# MyRC.net
KiCad netlist of a schematic drawn in Altium Designer
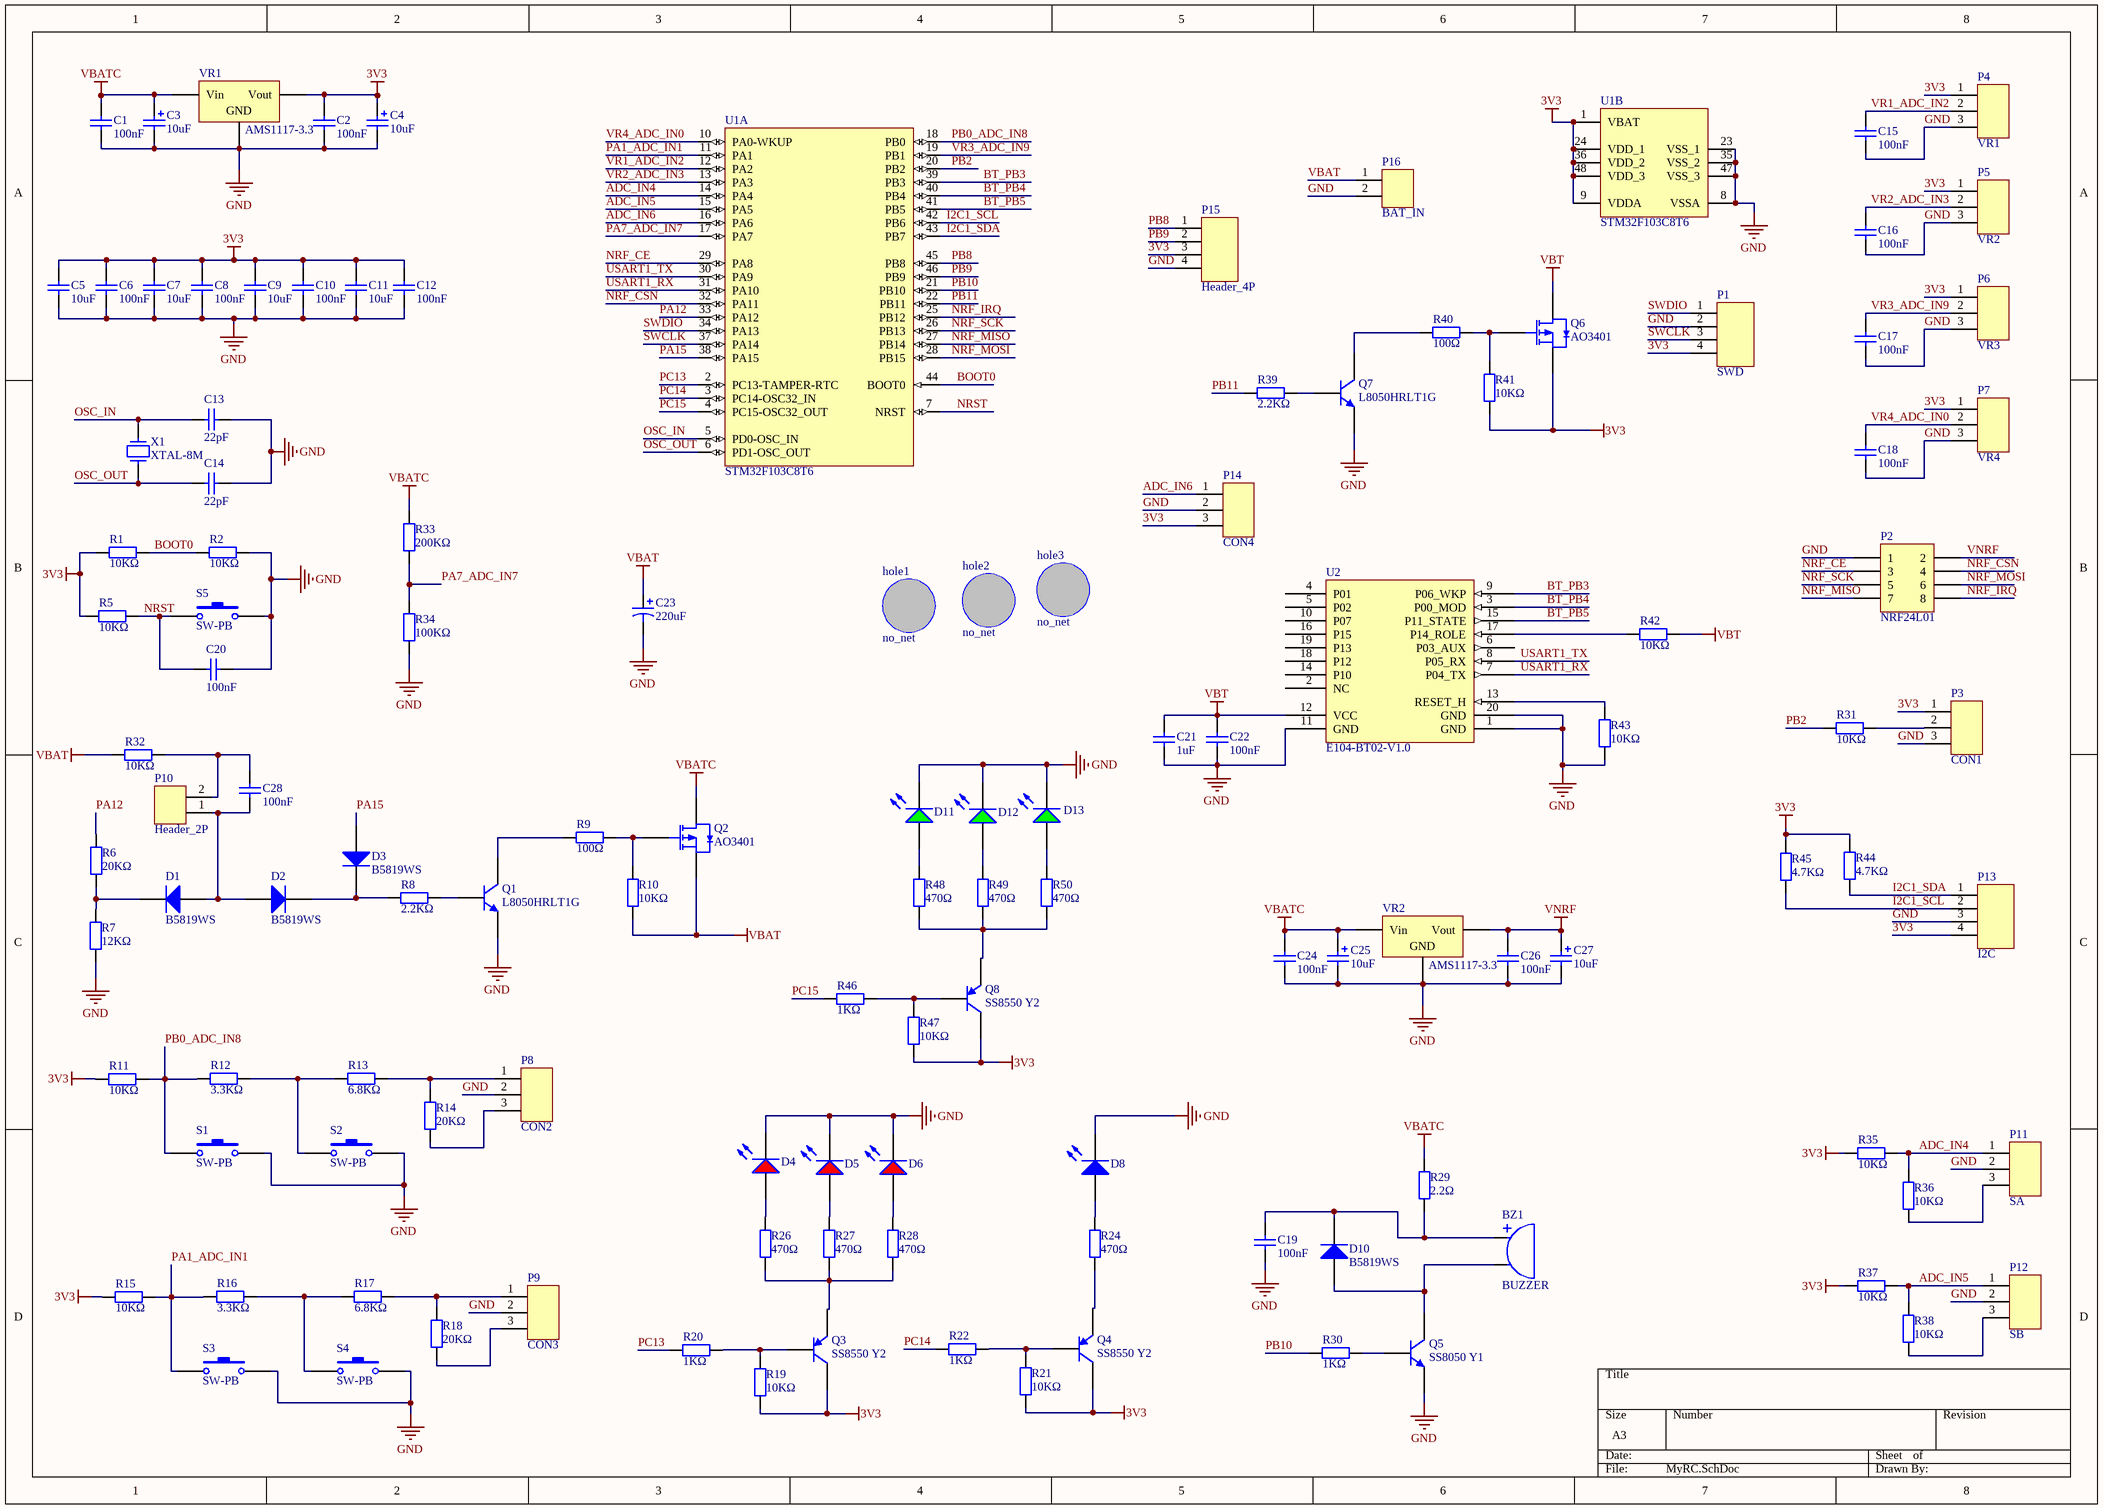
[diagram p0: MyRC.SchDoc]

(export (version "E")
  (design (tool "Eeschema 10.0.6"))
  (components
    (comp (ref "BZ1")
      (value "BUZZER")
      (footprint "BUZ_9MM")
      (description "Buzzer")
      (libsource (lib "General") (part "BUZZER"))
    )
    (comp (ref "C1")
      (value "100nF")
      (footprint "0603_C")
      (description "贴片电容")
      (libsource (lib "Miscellaneous Devices LC") (part "0603 220nF (224) 10% 25V"))
    )
    (comp (ref "C2")
      (value "100nF")
      (footprint "0603_C")
      (description "贴片电容")
      (libsource (lib "Miscellaneous Devices LC") (part "0603 220nF (224) 10% 25V"))
    )
    (comp (ref "C3")
      (value "10uF")
      (footprint "CASE-A_3216")
      (description "钽电容")
      (libsource (lib "Miscellaneous Devices LC") (part "3216 10uF (106) 10% 16V"))
    )
    (comp (ref "C4")
      (value "10uF")
      (footprint "CASE-A_3216")
      (description "钽电容")
      (libsource (lib "Miscellaneous Devices LC") (part "3216 10uF (106) 10% 16V"))
    )
    (comp (ref "C5")
      (value "10uF")
      (footprint "0603_C")
      (description "贴片电容")
      (libsource (lib "Miscellaneous Devices LC") (part "0603 2.2uF (225) 10% 16V"))
    )
    (comp (ref "C6")
      (value "100nF")
      (footprint "0603_C")
      (description "贴片电容")
      (libsource (lib "Miscellaneous Devices LC") (part "0603 2.2uF (225) 10% 16V"))
    )
    (comp (ref "C7")
      (value "10uF")
      (footprint "0603_C")
      (description "贴片电容")
      (libsource (lib "Miscellaneous Devices LC") (part "0603 2.2uF (225) 10% 16V"))
    )
    (comp (ref "C8")
      (value "100nF")
      (footprint "0603_C")
      (description "贴片电容")
      (libsource (lib "Miscellaneous Devices LC") (part "0603 2.2uF (225) 10% 16V"))
    )
    (comp (ref "C9")
      (value "10uF")
      (footprint "0603_C")
      (description "贴片电容")
      (libsource (lib "Miscellaneous Devices LC") (part "0603 2.2uF (225) 10% 16V"))
    )
    (comp (ref "C10")
      (value "100nF")
      (footprint "0603_C")
      (description "贴片电容")
      (libsource (lib "Miscellaneous Devices LC") (part "0603 2.2uF (225) 10% 16V"))
    )
    (comp (ref "C11")
      (value "10uF")
      (footprint "0603_C")
      (description "贴片电容")
      (libsource (lib "Miscellaneous Devices LC") (part "0603 2.2uF (225) 10% 16V"))
    )
    (comp (ref "C12")
      (value "100nF")
      (footprint "0603_C")
      (description "贴片电容")
      (libsource (lib "Miscellaneous Devices LC") (part "0603 2.2uF (225) 10% 16V"))
    )
    (comp (ref "C13")
      (value "22pF")
      (footprint "0603_C")
      (description "贴片电容")
      (libsource (lib "Miscellaneous Devices LC") (part "0603 2.2nF (222) 10% 50V"))
    )
    (comp (ref "C14")
      (value "22pF")
      (footprint "0603_C")
      (description "贴片电容")
      (libsource (lib "Miscellaneous Devices LC") (part "0603 2.2nF (222) 10% 50V"))
    )
    (comp (ref "C15")
      (value "100nF")
      (footprint "0603_C")
      (description "贴片电容")
      (libsource (lib "Miscellaneous Devices LC") (part "0603 2.2uF (225) 10% 16V"))
    )
    (comp (ref "C16")
      (value "100nF")
      (footprint "0603_C")
      (description "贴片电容")
      (libsource (lib "Miscellaneous Devices LC") (part "0603 2.2uF (225) 10% 16V"))
    )
    (comp (ref "C17")
      (value "100nF")
      (footprint "0603_C")
      (description "贴片电容")
      (libsource (lib "Miscellaneous Devices LC") (part "0603 2.2uF (225) 10% 16V"))
    )
    (comp (ref "C18")
      (value "100nF")
      (footprint "0603_C")
      (description "贴片电容")
      (libsource (lib "Miscellaneous Devices LC") (part "0603 2.2uF (225) 10% 16V"))
    )
    (comp (ref "C19")
      (value "100nF")
      (footprint "0603_C")
      (description "贴片电容")
      (libsource (lib "Miscellaneous Devices LC") (part "0603 2.2uF (225) 10% 16V"))
    )
    (comp (ref "C20")
      (value "100nF")
      (footprint "0603_C")
      (description "贴片电容")
      (libsource (lib "Miscellaneous Devices LC") (part "0603 2.2uF (225) 10% 16V"))
    )
    (comp (ref "C21")
      (value "1uF")
      (footprint "0603_C")
      (description "贴片电容")
      (libsource (lib "Miscellaneous Devices LC") (part "0603 2.2uF (225) 10% 16V"))
    )
    (comp (ref "C22")
      (value "100nF")
      (footprint "0603_C")
      (description "贴片电容")
      (libsource (lib "Miscellaneous Devices LC") (part "0603 2.2uF (225) 10% 16V"))
    )
    (comp (ref "C23")
      (value "220uF")
      (footprint "SMD_220uF")
      (description "Polarized Capacitor (Surface Mount)")
      (fields (field (name "Comment") "Cap Pol3") (field (name "PUBLISHER") "Altium Limited"))
      (libsource (lib "Miscellaneous Devices") (part "Cap Pol3"))
    )
    (comp (ref "C24")
      (value "100nF")
      (footprint "0603_C")
      (description "贴片电容")
      (libsource (lib "Miscellaneous Devices LC") (part "0603 220nF (224) 10% 25V"))
    )
    (comp (ref "C25")
      (value "10uF")
      (footprint "CASE-A_3216")
      (description "钽电容")
      (libsource (lib "Miscellaneous Devices LC") (part "3216 10uF (106) 10% 16V"))
    )
    (comp (ref "C26")
      (value "100nF")
      (footprint "0603_C")
      (description "贴片电容")
      (libsource (lib "Miscellaneous Devices LC") (part "0603 220nF (224) 10% 25V"))
    )
    (comp (ref "C27")
      (value "10uF")
      (footprint "CASE-A_3216")
      (description "钽电容")
      (libsource (lib "Miscellaneous Devices LC") (part "3216 10uF (106) 10% 16V"))
    )
    (comp (ref "C28")
      (value "100nF")
      (footprint "0603_C")
      (description "贴片电容")
      (libsource (lib "Miscellaneous Devices LC") (part "0603 1.2nF (122) 10% 50V"))
    )
    (comp (ref "D1")
      (value "B5819WS")
      (footprint "SOD-323")
      (description "二极管")
      (libsource (lib "Miscellaneous Devices LC") (part "SOD-323 1N4148WS T4"))
    )
    (comp (ref "D2")
      (value "B5819WS")
      (footprint "SOD-323")
      (description "二极管")
      (libsource (lib "Miscellaneous Devices LC") (part "SOD-323 1N4148WS T4"))
    )
    (comp (ref "D3")
      (value "B5819WS")
      (footprint "SOD-323")
      (description "二极管")
      (libsource (lib "Miscellaneous Devices LC") (part "SOD-323 1N4148WS T4"))
    )
    (comp (ref "D4")
      (value "红灯 0603")
      (footprint "0603_LED_S1")
      (description "发光二极管")
      (libsource (lib "Miscellaneous Devices LC") (part "0603 红灯"))
    )
    (comp (ref "D5")
      (value "红灯 0603")
      (footprint "0603_LED_S1")
      (description "发光二极管")
      (libsource (lib "Miscellaneous Devices LC") (part "0603 红灯"))
    )
    (comp (ref "D6")
      (value "红灯 0603")
      (footprint "0603_LED_S1")
      (description "发光二极管")
      (libsource (lib "Miscellaneous Devices LC") (part "0603 红灯"))
    )
    (comp (ref "D8")
      (value "蓝灯 0603")
      (footprint "0603_LED_S1")
      (description "发光二极管")
      (libsource (lib "Miscellaneous Devices LC") (part "0603 蓝灯"))
    )
    (comp (ref "D10")
      (value "B5819WS")
      (footprint "SOD-323")
      (description "二极管")
      (libsource (lib "Miscellaneous Devices LC") (part "SOD-323 1N4148WS T4"))
    )
    (comp (ref "D11")
      (value "绿灯 0603")
      (footprint "0603_LED_S1")
      (description "发光二极管")
      (libsource (lib "Miscellaneous Devices LC") (part "0603 绿灯"))
    )
    (comp (ref "D12")
      (value "绿灯 0603")
      (footprint "0603_LED_S1")
      (description "发光二极管")
      (libsource (lib "Miscellaneous Devices LC") (part "0603 绿灯"))
    )
    (comp (ref "D13")
      (value "绿灯 0603")
      (footprint "0603_LED_S1")
      (description "发光二极管")
      (libsource (lib "Miscellaneous Devices LC") (part "0603 绿灯"))
    )
    (comp (ref "hole1") (value "no_net") (footprint "Screw_holes") (libsource (lib "MyRC") (part "no_net")))
    (comp (ref "hole2") (value "no_net") (footprint "Screw_holes") (libsource (lib "MyRC") (part "no_net")))
    (comp (ref "hole3") (value "no_net") (footprint "Screw_holes") (libsource (lib "MyRC") (part "no_net")))
    (comp (ref "P1") (value "SWD") (footprint "SMD_1.25T_4P") (libsource (lib "MyRC") (part "Header_4P")))
    (comp (ref "P2")
      (value "NRF24L01")
      (footprint "HDR2X4")
      (description "Header, 4-Pin, Dual row")
      (fields (field (name "PUBLISHER") "Altium Limited"))
      (libsource (lib "Miscellaneous Connectors") (part "Header 4X2"))
    )
    (comp (ref "P3")
      (value "CON1")
      (footprint "SMD_1.25T_3P")
      (description "油门微动")
      (libsource (lib "MyRC") (part "Header_3P"))
    )
    (comp (ref "P4") (value "VR1") (footprint "SMD_1.25T_3P") (libsource (lib "MyRC") (part "Header_3P")))
    (comp (ref "P5") (value "VR2") (footprint "SMD_1.25T_3P") (libsource (lib "MyRC") (part "Header_3P")))
    (comp (ref "P6") (value "VR3") (footprint "SMD_1.25T_3P") (libsource (lib "MyRC") (part "Header_3P")))
    (comp (ref "P7") (value "VR4") (footprint "SMD_1.25T_3P") (libsource (lib "MyRC") (part "Header_3P")))
    (comp (ref "P8") (value "CON2") (footprint "SMD_1.25T_3P") (libsource (lib "MyRC") (part "Header_3P")))
    (comp (ref "P9") (value "CON3") (footprint "SMD_1.25T_3P") (libsource (lib "MyRC") (part "Header_3P")))
    (comp (ref "P10")
      (value "Header_2P")
      (footprint "SMD_1.25T_2P")
      (libsource (lib "") (part "Header_2P_1"))
    )
    (comp (ref "P11") (value "SA") (footprint "SMD_1.25T_3P") (libsource (lib "MyRC") (part "Header_3P")))
    (comp (ref "P12") (value "SB") (footprint "SMD_1.25T_3P") (libsource (lib "MyRC") (part "Header_3P")))
    (comp (ref "P13") (value "I2C") (footprint "SMD_1.25T_4P") (libsource (lib "MyRC") (part "Header_4P")))
    (comp (ref "P14") (value "CON4") (footprint "SMD_1.25T_3P") (libsource (lib "MyRC") (part "Header_3P")))
    (comp (ref "P15")
      (value "Header_4P")
      (footprint "SMD_1.25T_4P")
      (libsource (lib "MyRC") (part "Header_4P"))
    )
    (comp (ref "P16") (value "BAT_IN") (footprint "BAT_IN") (libsource (lib "MyRC") (part "Header_2P")))
    (comp (ref "Q1")
      (value "L8050HRLT1G")
      (footprint "SOT-23(SOT-23-3)")
      (description "三极管")
      (libsource (lib "Miscellaneous Devices LC") (part "SOT-23 SS8050 Y1"))
    )
    (comp (ref "Q2")
      (value "AO3401")
      (footprint "SOT-23-3L")
      (description "MOS(场效应管)")
      (libsource (lib "Miscellaneous Devices LC") (part "AO3401A P道沟 X13A15 SOT-23"))
    )
    (comp (ref "Q3")
      (value "SS8550 Y2")
      (footprint "SOT-23(SOT-23-3)")
      (description "三极管")
      (libsource (lib "Miscellaneous Devices LC") (part "SOT-23 SS8550 Y2"))
    )
    (comp (ref "Q4")
      (value "SS8550 Y2")
      (footprint "SOT-23(SOT-23-3)")
      (description "三极管")
      (libsource (lib "Miscellaneous Devices LC") (part "SOT-23 SS8550 Y2"))
    )
    (comp (ref "Q5")
      (value "SS8050 Y1")
      (footprint "SOT-23(SOT-23-3)")
      (description "三极管")
      (libsource (lib "Miscellaneous Devices LC") (part "SOT-23 SS8050 Y1"))
    )
    (comp (ref "Q6")
      (value "AO3401")
      (footprint "SOT-23-3L")
      (description "MOS(场效应管)")
      (libsource (lib "Miscellaneous Devices LC") (part "AO3401A P道沟 X13A15 SOT-23"))
    )
    (comp (ref "Q7")
      (value "L8050HRLT1G")
      (footprint "SOT-23(SOT-23-3)")
      (description "三极管")
      (libsource (lib "Miscellaneous Devices LC") (part "SOT-23 SS8050 Y1"))
    )
    (comp (ref "Q8")
      (value "SS8550 Y2")
      (footprint "SOT-23(SOT-23-3)")
      (description "三极管")
      (libsource (lib "Miscellaneous Devices LC") (part "SOT-23 SS8550 Y2"))
    )
    (comp (ref "R1")
      (value "10KΩ")
      (footprint "0603_R")
      (description "贴片电阻")
      (libsource (lib "Miscellaneous Devices LC") (part "0603 3.6KΩ (3601) 1%"))
    )
    (comp (ref "R2")
      (value "10KΩ")
      (footprint "0603_R")
      (description "贴片电阻")
      (libsource (lib "Miscellaneous Devices LC") (part "0603 3.6KΩ (3601) 1%"))
    )
    (comp (ref "R5")
      (value "10KΩ")
      (footprint "0603_R")
      (description "贴片电阻")
      (libsource (lib "Miscellaneous Devices LC") (part "0603 2KΩ (2001) 1%"))
    )
    (comp (ref "R6")
      (value "20KΩ")
      (footprint "0603_R")
      (description "贴片电阻")
      (libsource (lib "Miscellaneous Devices LC") (part "0603 3KΩ (3001) 1%"))
    )
    (comp (ref "R7")
      (value "12KΩ")
      (footprint "0603_R")
      (description "贴片电阻")
      (libsource (lib "") (part "0603 3KΩ (3001) 1%_2"))
    )
    (comp (ref "R8")
      (value "2.2KΩ")
      (footprint "0603_R")
      (description "贴片电阻")
      (libsource (lib "") (part "0603 3KΩ (3001) 1%_3"))
    )
    (comp (ref "R9")
      (value "100Ω")
      (footprint "0603_R")
      (description "贴片电阻")
      (libsource (lib "") (part "0603 3KΩ (3001) 1%_1"))
    )
    (comp (ref "R10")
      (value "10KΩ")
      (footprint "0603_R")
      (description "贴片电阻")
      (libsource (lib "Miscellaneous Devices LC") (part "0603 3KΩ (3001) 1%"))
    )
    (comp (ref "R11")
      (value "10KΩ")
      (footprint "0603_R")
      (description "贴片电阻")
      (libsource (lib "") (part "0603 1Ω (1R00) 1%_2"))
    )
    (comp (ref "R12")
      (value "3.3KΩ")
      (footprint "0603_R")
      (description "贴片电阻")
      (libsource (lib "") (part "0603 1Ω (1R00) 1%_2"))
    )
    (comp (ref "R13")
      (value "6.8KΩ")
      (footprint "0603_R")
      (description "贴片电阻")
      (libsource (lib "") (part "0603 1Ω (1R00) 1%_2"))
    )
    (comp (ref "R14")
      (value "20KΩ")
      (footprint "0603_R")
      (description "贴片电阻")
      (libsource (lib "") (part "0603 1Ω (1R00) 1%_1"))
    )
    (comp (ref "R15")
      (value "10KΩ")
      (footprint "0603_R")
      (description "贴片电阻")
      (libsource (lib "") (part "0603 1Ω (1R00) 1%_2"))
    )
    (comp (ref "R16")
      (value "3.3KΩ")
      (footprint "0603_R")
      (description "贴片电阻")
      (libsource (lib "") (part "0603 1Ω (1R00) 1%_2"))
    )
    (comp (ref "R17")
      (value "6.8KΩ")
      (footprint "0603_R")
      (description "贴片电阻")
      (libsource (lib "") (part "0603 1Ω (1R00) 1%_2"))
    )
    (comp (ref "R18")
      (value "20KΩ")
      (footprint "0603_R")
      (description "贴片电阻")
      (libsource (lib "") (part "0603 1Ω (1R00) 1%_1"))
    )
    (comp (ref "R19")
      (value "10KΩ")
      (footprint "0603_R")
      (description "贴片电阻")
      (libsource (lib "Miscellaneous Devices LC") (part "0603 1Ω (1R00) 1%"))
    )
    (comp (ref "R20")
      (value "1KΩ")
      (footprint "0603_R")
      (description "贴片电阻")
      (libsource (lib "") (part "0603 1Ω (1R00) 1%_2"))
    )
    (comp (ref "R21")
      (value "10KΩ")
      (footprint "0603_R")
      (description "贴片电阻")
      (libsource (lib "Miscellaneous Devices LC") (part "0603 1Ω (1R00) 1%"))
    )
    (comp (ref "R22")
      (value "1KΩ")
      (footprint "0603_R")
      (description "贴片电阻")
      (libsource (lib "") (part "0603 1Ω (1R00) 1%_2"))
    )
    (comp (ref "R24")
      (value "470Ω")
      (footprint "0603_R")
      (description "贴片电阻")
      (libsource (lib "Miscellaneous Devices LC") (part "0603 1Ω (1R00) 1%"))
    )
    (comp (ref "R26")
      (value "470Ω")
      (footprint "0603_R")
      (description "贴片电阻")
      (libsource (lib "Miscellaneous Devices LC") (part "0603 1Ω (1R00) 1%"))
    )
    (comp (ref "R27")
      (value "470Ω")
      (footprint "0603_R")
      (description "贴片电阻")
      (libsource (lib "Miscellaneous Devices LC") (part "0603 1Ω (1R00) 1%"))
    )
    (comp (ref "R28")
      (value "470Ω")
      (footprint "0603_R")
      (description "贴片电阻")
      (libsource (lib "Miscellaneous Devices LC") (part "0603 1Ω (1R00) 1%"))
    )
    (comp (ref "R29")
      (value "2.2Ω")
      (footprint "0603_R")
      (description "贴片电阻")
      (libsource (lib "Miscellaneous Devices LC") (part "0603 1Ω (1R00) 1%"))
    )
    (comp (ref "R30")
      (value "1KΩ")
      (footprint "0603_R")
      (description "贴片电阻")
      (libsource (lib "") (part "0603 1Ω (1R00) 1%_2"))
    )
    (comp (ref "R31")
      (value "10KΩ")
      (footprint "0603_R")
      (description "贴片电阻")
      (libsource (lib "") (part "0603 3KΩ (3001) 1%_1"))
    )
    (comp (ref "R32")
      (value "10KΩ")
      (footprint "0603_R")
      (description "贴片电阻")
      (libsource (lib "") (part "0603 3KΩ (3001) 1%_1"))
    )
    (comp (ref "R33")
      (value "200KΩ")
      (footprint "0603_R")
      (description "贴片电阻")
      (libsource (lib "Miscellaneous Devices LC") (part "0603 3KΩ (3001) 1%"))
    )
    (comp (ref "R34")
      (value "100KΩ")
      (footprint "0603_R")
      (description "贴片电阻")
      (libsource (lib "Miscellaneous Devices LC") (part "0603 3KΩ (3001) 1%"))
    )
    (comp (ref "R35")
      (value "10KΩ")
      (footprint "0603_R")
      (description "贴片电阻")
      (libsource (lib "") (part "0603 1Ω (1R00) 1%_2"))
    )
    (comp (ref "R36")
      (value "10KΩ")
      (footprint "0603_R")
      (description "贴片电阻")
      (libsource (lib "") (part "0603 1Ω (1R00) 1%_1"))
    )
    (comp (ref "R37")
      (value "10KΩ")
      (footprint "0603_R")
      (description "贴片电阻")
      (libsource (lib "") (part "0603 1Ω (1R00) 1%_2"))
    )
    (comp (ref "R38")
      (value "10KΩ")
      (footprint "0603_R")
      (description "贴片电阻")
      (libsource (lib "") (part "0603 1Ω (1R00) 1%_1"))
    )
    (comp (ref "R39")
      (value "2.2KΩ")
      (footprint "0603_R")
      (description "贴片电阻")
      (libsource (lib "") (part "0603 3KΩ (3001) 1%_3"))
    )
    (comp (ref "R40")
      (value "100Ω")
      (footprint "0603_R")
      (description "贴片电阻")
      (libsource (lib "") (part "0603 3KΩ (3001) 1%_1"))
    )
    (comp (ref "R41")
      (value "10KΩ")
      (footprint "0603_R")
      (description "贴片电阻")
      (libsource (lib "Miscellaneous Devices LC") (part "0603 3KΩ (3001) 1%"))
    )
    (comp (ref "R42")
      (value "10KΩ")
      (footprint "0603_R")
      (description "贴片电阻")
      (libsource (lib "") (part "0603 3KΩ (3001) 1%_1"))
    )
    (comp (ref "R43")
      (value "10KΩ")
      (footprint "0603_R")
      (description "贴片电阻")
      (libsource (lib "") (part "0603 3KΩ (3001) 1%_2"))
    )
    (comp (ref "R44")
      (value "4.7KΩ")
      (footprint "0603_R")
      (description "贴片电阻")
      (libsource (lib "Miscellaneous Devices LC") (part "0603 3KΩ (3001) 1%"))
    )
    (comp (ref "R45")
      (value "4.7KΩ")
      (footprint "0603_R")
      (description "贴片电阻")
      (libsource (lib "Miscellaneous Devices LC") (part "0603 3KΩ (3001) 1%"))
    )
    (comp (ref "R46")
      (value "1KΩ")
      (footprint "0603_R")
      (description "贴片电阻")
      (libsource (lib "") (part "0603 1Ω (1R00) 1%_2"))
    )
    (comp (ref "R47")
      (value "10KΩ")
      (footprint "0603_R")
      (description "贴片电阻")
      (libsource (lib "Miscellaneous Devices LC") (part "0603 1Ω (1R00) 1%"))
    )
    (comp (ref "R48")
      (value "470Ω")
      (footprint "0603_R")
      (description "贴片电阻")
      (libsource (lib "Miscellaneous Devices LC") (part "0603 1Ω (1R00) 1%"))
    )
    (comp (ref "R49")
      (value "470Ω")
      (footprint "0603_R")
      (description "贴片电阻")
      (libsource (lib "Miscellaneous Devices LC") (part "0603 1Ω (1R00) 1%"))
    )
    (comp (ref "R50")
      (value "470Ω")
      (footprint "0603_R")
      (description "贴片电阻")
      (libsource (lib "Miscellaneous Devices LC") (part "0603 1Ω (1R00) 1%"))
    )
    (comp (ref "S1")
      (value "SW-PB")
      (footprint "SMD_KEY_6MM")
      (description "Switch")
      (fields (field (name "PUBLISHER") "Altium Limited"))
      (libsource (lib "Miscellaneous Devices") (part "SW-PB"))
    )
    (comp (ref "S2")
      (value "SW-PB")
      (footprint "SMD_KEY_6MM")
      (description "Switch")
      (fields (field (name "PUBLISHER") "Altium Limited"))
      (libsource (lib "Miscellaneous Devices") (part "SW-PB"))
    )
    (comp (ref "S3")
      (value "SW-PB")
      (footprint "SMD_KEY_6MM")
      (description "Switch")
      (fields (field (name "PUBLISHER") "Altium Limited"))
      (libsource (lib "Miscellaneous Devices") (part "SW-PB"))
    )
    (comp (ref "S4")
      (value "SW-PB")
      (footprint "SMD_KEY_6MM")
      (description "Switch")
      (fields (field (name "PUBLISHER") "Altium Limited"))
      (libsource (lib "Miscellaneous Devices") (part "SW-PB"))
    )
    (comp (ref "S5")
      (value "SW-PB")
      (footprint "SMD_KEY_4P")
      (description "Switch")
      (fields (field (name "PUBLISHER") "Altium Limited"))
      (libsource (lib "Miscellaneous Devices") (part "SW-PB"))
    )
    (comp (ref "U1")
      (value "STM32F103C8T6")
      (footprint "STM-LQFP48_N")
      (libsource (lib "STMicroelectronics STM32 F1") (part "STM32F103C8T6"))
    )
    (comp (ref "U2")
      (value "E104-BT02-V1.0")
      (footprint "PE104-BT02")
      (libsource (lib "MyRC") (part "E104-BT02-V1.0"))
    )
    (comp (ref "VR1")
      (value "AMS1117-3.3")
      (footprint "SOT-223")
      (description "低压差线性稳压(LDO)")
      (libsource (lib "Miscellaneous Devices LC") (part "SOT-223 AMS1117-3.3"))
    )
    (comp (ref "VR2")
      (value "AMS1117-3.3")
      (footprint "SOT-223")
      (description "低压差线性稳压(LDO)")
      (libsource (lib "Miscellaneous Devices LC") (part "SOT-223 AMS1117-3.3"))
    )
    (comp (ref "X1")
      (value "XTAL-8M")
      (footprint "XTAL_N")
      (description "Crystal")
      (libsource (lib "General") (part "XTAL-2"))
    )
  )
  (nets
    (net (code "1") (name "/ADC_IN4") (class "Default")
      (node (ref "P11") (pin "1") (pinfunction "1_1") (pintype "passive"))
      (node (ref "R35") (pin "1") (pinfunction "1_1") (pintype "passive"))
      (node (ref "R36") (pin "1") (pinfunction "1_1") (pintype "passive"))
      (node (ref "U1") (pin "14") (pinfunction "PA4_14") (pintype "bidirectional"))
    )
    (net (code "2") (name "/ADC_IN5") (class "Default")
      (node (ref "P12") (pin "1") (pinfunction "1_1") (pintype "passive"))
      (node (ref "R37") (pin "1") (pinfunction "1_1") (pintype "passive"))
      (node (ref "R38") (pin "1") (pinfunction "1_1") (pintype "passive"))
      (node (ref "U1") (pin "15") (pinfunction "PA5_15") (pintype "bidirectional"))
    )
    (net (code "3") (name "/ADC_IN6") (class "Default")
      (node (ref "P14") (pin "1") (pinfunction "1_1") (pintype "passive"))
      (node (ref "U1") (pin "16") (pinfunction "PA6_16") (pintype "bidirectional"))
    )
    (net (code "4") (name "/BOOT0") (class "Default")
      (node (ref "R1") (pin "2") (pinfunction "2_2") (pintype "passive"))
      (node (ref "R2") (pin "1") (pinfunction "1_1") (pintype "passive"))
      (node (ref "U1") (pin "44") (pinfunction "BOOT0_44") (pintype "input"))
    )
    (net (code "5") (name "/BT_PB3") (class "Default")
      (node (ref "U1") (pin "39") (pinfunction "PB3_39") (pintype "bidirectional"))
      (node (ref "U2") (pin "9") (pinfunction "P06_WKP_9") (pintype "input"))
    )
    (net (code "6") (name "/BT_PB4") (class "Default")
      (node (ref "U1") (pin "40") (pinfunction "PB4_40") (pintype "bidirectional"))
      (node (ref "U2") (pin "3") (pinfunction "P00_MOD_3") (pintype "input"))
    )
    (net (code "7") (name "/BT_PB5") (class "Default")
      (node (ref "U1") (pin "41") (pinfunction "PB5_41") (pintype "bidirectional"))
      (node (ref "U2") (pin "15") (pinfunction "P11_STATE_15") (pintype "output"))
    )
    (net (code "8") (name "/I2C1_SCL") (class "Default")
      (node (ref "P13") (pin "2") (pinfunction "2_2") (pintype "passive"))
      (node (ref "R45") (pin "1") (pinfunction "1_1") (pintype "passive"))
      (node (ref "U1") (pin "42") (pinfunction "PB6_42") (pintype "bidirectional"))
    )
    (net (code "9") (name "/I2C1_SDA") (class "Default")
      (node (ref "P13") (pin "1") (pinfunction "1_1") (pintype "passive"))
      (node (ref "R44") (pin "1") (pinfunction "1_1") (pintype "passive"))
      (node (ref "U1") (pin "43") (pinfunction "PB7_43") (pintype "bidirectional"))
    )
    (net (code "10") (name "/NRF_CE") (class "Default")
      (node (ref "P2") (pin "3") (pinfunction "3_3") (pintype "passive"))
      (node (ref "U1") (pin "29") (pinfunction "PA8_29") (pintype "bidirectional"))
    )
    (net (code "11") (name "/NRF_CSN") (class "Default")
      (node (ref "P2") (pin "4") (pinfunction "4_4") (pintype "passive"))
      (node (ref "U1") (pin "32") (pinfunction "PA11_32") (pintype "bidirectional"))
    )
    (net (code "12") (name "/NRF_IRQ") (class "Default")
      (node (ref "P2") (pin "8") (pinfunction "8_8") (pintype "passive"))
      (node (ref "U1") (pin "25") (pinfunction "PB12_25") (pintype "bidirectional"))
    )
    (net (code "13") (name "/NRF_MISO") (class "Default")
      (node (ref "P2") (pin "7") (pinfunction "7_7") (pintype "passive"))
      (node (ref "U1") (pin "27") (pinfunction "PB14_27") (pintype "bidirectional"))
    )
    (net (code "14") (name "/NRF_MOSI") (class "Default")
      (node (ref "P2") (pin "6") (pinfunction "6_6") (pintype "passive"))
      (node (ref "U1") (pin "28") (pinfunction "PB15_28") (pintype "bidirectional"))
    )
    (net (code "15") (name "/NRF_SCK") (class "Default")
      (node (ref "P2") (pin "5") (pinfunction "5_5") (pintype "passive"))
      (node (ref "U1") (pin "26") (pinfunction "PB13_26") (pintype "bidirectional"))
    )
    (net (code "16") (name "/NRST") (class "Default")
      (node (ref "C20") (pin "2") (pinfunction "2_2") (pintype "passive"))
      (node (ref "R5") (pin "2") (pinfunction "2_2") (pintype "passive"))
      (node (ref "S5") (pin "1") (pinfunction "1_1") (pintype "passive"))
      (node (ref "U1") (pin "7") (pinfunction "NRST_7") (pintype "bidirectional"))
    )
    (net (code "17") (name "/OSC_IN") (class "Default")
      (node (ref "C13") (pin "1") (pinfunction "1_1") (pintype "passive"))
      (node (ref "U1") (pin "5") (pinfunction "PD0-OSC_IN_5") (pintype "bidirectional"))
      (node (ref "X1") (pin "1") (pinfunction "1_1") (pintype "passive"))
    )
    (net (code "18") (name "/OSC_OUT") (class "Default")
      (node (ref "C14") (pin "1") (pinfunction "1_1") (pintype "passive"))
      (node (ref "U1") (pin "6") (pinfunction "PD1-OSC_OUT_6") (pintype "bidirectional"))
      (node (ref "X1") (pin "2") (pinfunction "2_2") (pintype "passive"))
    )
    (net (code "19") (name "/PA1_ADC_IN1") (class "Default")
      (node (ref "R15") (pin "1") (pinfunction "1_1") (pintype "passive"))
      (node (ref "R16") (pin "2") (pinfunction "2_2") (pintype "passive"))
      (node (ref "S3") (pin "1") (pinfunction "1_1") (pintype "passive"))
      (node (ref "U1") (pin "11") (pinfunction "PA1_11") (pintype "bidirectional"))
    )
    (net (code "20") (name "/PA7_ADC_IN7") (class "Default")
      (node (ref "R33") (pin "1") (pinfunction "1_1") (pintype "passive"))
      (node (ref "R34") (pin "2") (pinfunction "2_2") (pintype "passive"))
      (node (ref "U1") (pin "17") (pinfunction "PA7_17") (pintype "bidirectional"))
    )
    (net (code "21") (name "/PA12") (class "Default")
      (node (ref "R6") (pin "2") (pinfunction "2_2") (pintype "passive"))
      (node (ref "U1") (pin "33") (pinfunction "PA12_33") (pintype "bidirectional"))
    )
    (net (code "22") (name "/PA15") (class "Default")
      (node (ref "D3") (pin "1") (pinfunction "A_1") (pintype "passive"))
      (node (ref "U1") (pin "38") (pinfunction "PA15_38") (pintype "bidirectional"))
    )
    (net (code "23") (name "/PB0_ADC_IN8") (class "Default")
      (node (ref "R11") (pin "1") (pinfunction "1_1") (pintype "passive"))
      (node (ref "R12") (pin "2") (pinfunction "2_2") (pintype "passive"))
      (node (ref "S1") (pin "1") (pinfunction "1_1") (pintype "passive"))
      (node (ref "U1") (pin "18") (pinfunction "PB0_18") (pintype "bidirectional"))
    )
    (net (code "24") (name "/PB2") (class "Default")
      (node (ref "R31") (pin "2") (pinfunction "2_2") (pintype "passive"))
      (node (ref "U1") (pin "20") (pinfunction "PB2_20") (pintype "bidirectional"))
    )
    (net (code "25") (name "/PB8") (class "Default")
      (node (ref "P15") (pin "1") (pinfunction "1_1") (pintype "passive"))
      (node (ref "U1") (pin "45") (pinfunction "PB8_45") (pintype "bidirectional"))
    )
    (net (code "26") (name "/PB9") (class "Default")
      (node (ref "P15") (pin "2") (pinfunction "2_2") (pintype "passive"))
      (node (ref "U1") (pin "46") (pinfunction "PB9_46") (pintype "bidirectional"))
    )
    (net (code "27") (name "/PB10") (class "Default")
      (node (ref "R30") (pin "2") (pinfunction "2_2") (pintype "passive"))
      (node (ref "U1") (pin "21") (pinfunction "PB10_21") (pintype "bidirectional"))
    )
    (net (code "28") (name "/PB11") (class "Default")
      (node (ref "R39") (pin "1") (pinfunction "1_1") (pintype "passive"))
      (node (ref "U1") (pin "22") (pinfunction "PB11_22") (pintype "bidirectional"))
    )
    (net (code "29") (name "/PC13") (class "Default")
      (node (ref "R20") (pin "2") (pinfunction "2_2") (pintype "passive"))
      (node (ref "U1") (pin "2") (pinfunction "PC13-TAMPER-RTC_2") (pintype "bidirectional"))
    )
    (net (code "30") (name "/PC14") (class "Default")
      (node (ref "R22") (pin "2") (pinfunction "2_2") (pintype "passive"))
      (node (ref "U1") (pin "3") (pinfunction "PC14-OSC32_IN_3") (pintype "bidirectional"))
    )
    (net (code "31") (name "/PC15") (class "Default")
      (node (ref "R46") (pin "2") (pinfunction "2_2") (pintype "passive"))
      (node (ref "U1") (pin "4") (pinfunction "PC15-OSC32_OUT_4") (pintype "bidirectional"))
    )
    (net (code "32") (name "/SWCLK") (class "Default")
      (node (ref "P1") (pin "3") (pinfunction "3_3") (pintype "passive"))
      (node (ref "U1") (pin "37") (pinfunction "PA14_37") (pintype "bidirectional"))
    )
    (net (code "33") (name "/SWDIO") (class "Default")
      (node (ref "P1") (pin "1") (pinfunction "1_1") (pintype "passive"))
      (node (ref "U1") (pin "34") (pinfunction "PA13_34") (pintype "bidirectional"))
    )
    (net (code "34") (name "/USART1_RX") (class "Default")
      (node (ref "U1") (pin "31") (pinfunction "PA10_31") (pintype "bidirectional"))
      (node (ref "U2") (pin "7") (pinfunction "P04_TX_7") (pintype "output"))
    )
    (net (code "35") (name "/USART1_TX") (class "Default")
      (node (ref "U1") (pin "30") (pinfunction "PA9_30") (pintype "bidirectional"))
      (node (ref "U2") (pin "8") (pinfunction "P05_RX_8") (pintype "input"))
    )
    (net (code "36") (name "/VR1_ADC_IN2") (class "Default")
      (node (ref "C15") (pin "2") (pinfunction "2_2") (pintype "passive"))
      (node (ref "P4") (pin "2") (pinfunction "2_2") (pintype "passive"))
      (node (ref "U1") (pin "12") (pinfunction "PA2_12") (pintype "bidirectional"))
    )
    (net (code "37") (name "/VR2_ADC_IN3") (class "Default")
      (node (ref "C16") (pin "2") (pinfunction "2_2") (pintype "passive"))
      (node (ref "P5") (pin "2") (pinfunction "2_2") (pintype "passive"))
      (node (ref "U1") (pin "13") (pinfunction "PA3_13") (pintype "bidirectional"))
    )
    (net (code "38") (name "/VR3_ADC_IN9") (class "Default")
      (node (ref "C17") (pin "2") (pinfunction "2_2") (pintype "passive"))
      (node (ref "P6") (pin "2") (pinfunction "2_2") (pintype "passive"))
      (node (ref "U1") (pin "19") (pinfunction "PB1_19") (pintype "bidirectional"))
    )
    (net (code "39") (name "/VR4_ADC_IN0") (class "Default")
      (node (ref "C18") (pin "2") (pinfunction "2_2") (pintype "passive"))
      (node (ref "P7") (pin "2") (pinfunction "2_2") (pintype "passive"))
      (node (ref "U1") (pin "10") (pinfunction "PA0-WKUP_10") (pintype "bidirectional"))
    )
    (net (code "40") (name "3V3") (class "Default")
      (node (ref "C10") (pin "2") (pinfunction "2_2") (pintype "passive"))
      (node (ref "C11") (pin "2") (pinfunction "2_2") (pintype "passive"))
      (node (ref "C12") (pin "2") (pinfunction "2_2") (pintype "passive"))
      (node (ref "C2") (pin "2") (pinfunction "2_2") (pintype "passive"))
      (node (ref "C4") (pin "1") (pinfunction "1_1") (pintype "passive"))
      (node (ref "C5") (pin "2") (pinfunction "2_2") (pintype "passive"))
      (node (ref "C6") (pin "2") (pinfunction "2_2") (pintype "passive"))
      (node (ref "C7") (pin "2") (pinfunction "2_2") (pintype "passive"))
      (node (ref "C8") (pin "2") (pinfunction "2_2") (pintype "passive"))
      (node (ref "C9") (pin "2") (pinfunction "2_2") (pintype "passive"))
      (node (ref "P1") (pin "4") (pinfunction "4_4") (pintype "passive"))
      (node (ref "P13") (pin "4") (pinfunction "4_4") (pintype "passive"))
      (node (ref "P14") (pin "3") (pinfunction "3_3") (pintype "passive"))
      (node (ref "P15") (pin "3") (pinfunction "3_3") (pintype "passive"))
      (node (ref "P3") (pin "1") (pinfunction "1_1") (pintype "passive"))
      (node (ref "P4") (pin "1") (pinfunction "1_1") (pintype "passive"))
      (node (ref "P5") (pin "1") (pinfunction "1_1") (pintype "passive"))
      (node (ref "P6") (pin "1") (pinfunction "1_1") (pintype "passive"))
      (node (ref "P7") (pin "1") (pinfunction "1_1") (pintype "passive"))
      (node (ref "Q3") (pin "3") (pinfunction "C_3") (pintype "passive"))
      (node (ref "Q4") (pin "3") (pinfunction "C_3") (pintype "passive"))
      (node (ref "Q6") (pin "2") (pinfunction "S_2") (pintype "passive"))
      (node (ref "Q8") (pin "3") (pinfunction "C_3") (pintype "passive"))
      (node (ref "R1") (pin "1") (pinfunction "1_1") (pintype "passive"))
      (node (ref "R11") (pin "2") (pinfunction "2_2") (pintype "passive"))
      (node (ref "R15") (pin "2") (pinfunction "2_2") (pintype "passive"))
      (node (ref "R19") (pin "1") (pinfunction "1_1") (pintype "passive"))
      (node (ref "R21") (pin "1") (pinfunction "1_1") (pintype "passive"))
      (node (ref "R35") (pin "2") (pinfunction "2_2") (pintype "passive"))
      (node (ref "R37") (pin "2") (pinfunction "2_2") (pintype "passive"))
      (node (ref "R41") (pin "1") (pinfunction "1_1") (pintype "passive"))
      (node (ref "R44") (pin "2") (pinfunction "2_2") (pintype "passive"))
      (node (ref "R45") (pin "2") (pinfunction "2_2") (pintype "passive"))
      (node (ref "R47") (pin "1") (pinfunction "1_1") (pintype "passive"))
      (node (ref "R5") (pin "1") (pinfunction "1_1") (pintype "passive"))
      (node (ref "U1") (pin "1") (pinfunction "VBAT_1") (pintype "power_in"))
      (node (ref "U1") (pin "24") (pinfunction "VDD_1_24") (pintype "power_in"))
      (node (ref "U1") (pin "36") (pinfunction "VDD_2_36") (pintype "power_in"))
      (node (ref "U1") (pin "48") (pinfunction "VDD_3_48") (pintype "power_in"))
      (node (ref "U1") (pin "9") (pinfunction "VDDA_9") (pintype "power_in"))
      (node (ref "VR1") (pin "2") (pinfunction "Vout_2") (pintype "passive"))
    )
    (net (code "41") (name "GND") (class "Default")
      (node (ref "C1") (pin "1") (pinfunction "1_1") (pintype "passive"))
      (node (ref "C10") (pin "1") (pinfunction "1_1") (pintype "passive"))
      (node (ref "C11") (pin "1") (pinfunction "1_1") (pintype "passive"))
      (node (ref "C12") (pin "1") (pinfunction "1_1") (pintype "passive"))
      (node (ref "C13") (pin "2") (pinfunction "2_2") (pintype "passive"))
      (node (ref "C14") (pin "2") (pinfunction "2_2") (pintype "passive"))
      (node (ref "C15") (pin "1") (pinfunction "1_1") (pintype "passive"))
      (node (ref "C16") (pin "1") (pinfunction "1_1") (pintype "passive"))
      (node (ref "C17") (pin "1") (pinfunction "1_1") (pintype "passive"))
      (node (ref "C18") (pin "1") (pinfunction "1_1") (pintype "passive"))
      (node (ref "C19") (pin "1") (pinfunction "1_1") (pintype "passive"))
      (node (ref "C2") (pin "1") (pinfunction "1_1") (pintype "passive"))
      (node (ref "C20") (pin "1") (pinfunction "1_1") (pintype "passive"))
      (node (ref "C21") (pin "1") (pinfunction "1_1") (pintype "passive"))
      (node (ref "C22") (pin "1") (pinfunction "1_1") (pintype "passive"))
      (node (ref "C23") (pin "2") (pinfunction "2_2") (pintype "passive"))
      (node (ref "C24") (pin "1") (pinfunction "1_1") (pintype "passive"))
      (node (ref "C25") (pin "2") (pinfunction "2_2") (pintype "passive"))
      (node (ref "C26") (pin "1") (pinfunction "1_1") (pintype "passive"))
      (node (ref "C27") (pin "2") (pinfunction "2_2") (pintype "passive"))
      (node (ref "C3") (pin "2") (pinfunction "2_2") (pintype "passive"))
      (node (ref "C4") (pin "2") (pinfunction "2_2") (pintype "passive"))
      (node (ref "C5") (pin "1") (pinfunction "1_1") (pintype "passive"))
      (node (ref "C6") (pin "1") (pinfunction "1_1") (pintype "passive"))
      (node (ref "C7") (pin "1") (pinfunction "1_1") (pintype "passive"))
      (node (ref "C8") (pin "1") (pinfunction "1_1") (pintype "passive"))
      (node (ref "C9") (pin "1") (pinfunction "1_1") (pintype "passive"))
      (node (ref "D11") (pin "K") (pinfunction "K_K") (pintype "passive"))
      (node (ref "D12") (pin "K") (pinfunction "K_K") (pintype "passive"))
      (node (ref "D13") (pin "K") (pinfunction "K_K") (pintype "passive"))
      (node (ref "D4") (pin "K") (pinfunction "K_K") (pintype "passive"))
      (node (ref "D5") (pin "K") (pinfunction "K_K") (pintype "passive"))
      (node (ref "D6") (pin "K") (pinfunction "K_K") (pintype "passive"))
      (node (ref "D8") (pin "K") (pinfunction "K_K") (pintype "passive"))
      (node (ref "P1") (pin "2") (pinfunction "2_2") (pintype "passive"))
      (node (ref "P11") (pin "2") (pinfunction "2_2") (pintype "passive"))
      (node (ref "P12") (pin "2") (pinfunction "2_2") (pintype "passive"))
      (node (ref "P13") (pin "3") (pinfunction "3_3") (pintype "passive"))
      (node (ref "P14") (pin "2") (pinfunction "2_2") (pintype "passive"))
      (node (ref "P15") (pin "4") (pinfunction "4_4") (pintype "passive"))
      (node (ref "P16") (pin "2") (pinfunction "2_2") (pintype "passive"))
      (node (ref "P2") (pin "1") (pinfunction "1_1") (pintype "passive"))
      (node (ref "P3") (pin "3") (pinfunction "3_3") (pintype "passive"))
      (node (ref "P4") (pin "3") (pinfunction "3_3") (pintype "passive"))
      (node (ref "P5") (pin "3") (pinfunction "3_3") (pintype "passive"))
      (node (ref "P6") (pin "3") (pinfunction "3_3") (pintype "passive"))
      (node (ref "P7") (pin "3") (pinfunction "3_3") (pintype "passive"))
      (node (ref "P8") (pin "2") (pinfunction "2_2") (pintype "passive"))
      (node (ref "P9") (pin "2") (pinfunction "2_2") (pintype "passive"))
      (node (ref "Q1") (pin "2") (pinfunction "E_2") (pintype "passive"))
      (node (ref "Q5") (pin "2") (pinfunction "E_2") (pintype "passive"))
      (node (ref "Q7") (pin "2") (pinfunction "E_2") (pintype "passive"))
      (node (ref "R2") (pin "2") (pinfunction "2_2") (pintype "passive"))
      (node (ref "R34") (pin "1") (pinfunction "1_1") (pintype "passive"))
      (node (ref "R43") (pin "2") (pinfunction "2_2") (pintype "passive"))
      (node (ref "R7") (pin "2") (pinfunction "2_2") (pintype "passive"))
      (node (ref "S1") (pin "2") (pinfunction "2_2") (pintype "passive"))
      (node (ref "S2") (pin "2") (pinfunction "2_2") (pintype "passive"))
      (node (ref "S3") (pin "2") (pinfunction "2_2") (pintype "passive"))
      (node (ref "S4") (pin "2") (pinfunction "2_2") (pintype "passive"))
      (node (ref "S5") (pin "2") (pinfunction "2_2") (pintype "passive"))
      (node (ref "U1") (pin "23") (pinfunction "VSS_1_23") (pintype "power_in"))
      (node (ref "U1") (pin "35") (pinfunction "VSS_2_35") (pintype "power_in"))
      (node (ref "U1") (pin "47") (pinfunction "VSS_3_47") (pintype "power_in"))
      (node (ref "U1") (pin "8") (pinfunction "VSSA_8") (pintype "power_in"))
      (node (ref "U2") (pin "1") (pinfunction "GND_1") (pintype "power_in"))
      (node (ref "U2") (pin "11") (pinfunction "GND_11") (pintype "power_in"))
      (node (ref "U2") (pin "20") (pinfunction "GND_20") (pintype "power_in"))
      (node (ref "VR1") (pin "1") (pinfunction "GND_1") (pintype "passive"))
      (node (ref "VR2") (pin "1") (pinfunction "GND_1") (pintype "passive"))
    )
    (net (code "42") (name "Net-(C28-Pad2)") (class "Default")
      (node (ref "C28") (pin "2") (pinfunction "2_2") (pintype "passive"))
      (node (ref "P10") (pin "2") (pinfunction "2_2") (pintype "passive"))
      (node (ref "R32") (pin "1") (pinfunction "1_1") (pintype "passive"))
    )
    (net (code "43") (name "Net-(D1-A)") (class "Default")
      (node (ref "C28") (pin "1") (pinfunction "1_1") (pintype "passive"))
      (node (ref "D1") (pin "1") (pinfunction "A_1") (pintype "passive"))
      (node (ref "D2") (pin "1") (pinfunction "A_1") (pintype "passive"))
      (node (ref "P10") (pin "1") (pinfunction "1_1") (pintype "passive"))
    )
    (net (code "44") (name "Net-(D1-K)") (class "Default")
      (node (ref "D1") (pin "2") (pinfunction "K_2") (pintype "passive"))
      (node (ref "R6") (pin "1") (pinfunction "1_1") (pintype "passive"))
      (node (ref "R7") (pin "1") (pinfunction "1_1") (pintype "passive"))
    )
    (net (code "45") (name "Net-(D2-K)") (class "Default")
      (node (ref "D2") (pin "2") (pinfunction "K_2") (pintype "passive"))
      (node (ref "D3") (pin "2") (pinfunction "K_2") (pintype "passive"))
      (node (ref "R8") (pin "1") (pinfunction "1_1") (pintype "passive"))
    )
    (net (code "46") (name "Net-(D4-PadA)") (class "Default")
      (node (ref "D4") (pin "A") (pinfunction "A_A") (pintype "passive"))
      (node (ref "R26") (pin "2") (pinfunction "2_2") (pintype "passive"))
    )
    (net (code "47") (name "Net-(D5-PadA)") (class "Default")
      (node (ref "D5") (pin "A") (pinfunction "A_A") (pintype "passive"))
      (node (ref "R27") (pin "2") (pinfunction "2_2") (pintype "passive"))
    )
    (net (code "48") (name "Net-(D6-PadA)") (class "Default")
      (node (ref "D6") (pin "A") (pinfunction "A_A") (pintype "passive"))
      (node (ref "R28") (pin "2") (pinfunction "2_2") (pintype "passive"))
    )
    (net (code "49") (name "Net-(D8-PadA)") (class "Default")
      (node (ref "D8") (pin "A") (pinfunction "A_A") (pintype "passive"))
      (node (ref "R24") (pin "2") (pinfunction "2_2") (pintype "passive"))
    )
    (net (code "50") (name "Net-(D10-A)") (class "Default")
      (node (ref "BZ1") (pin "2") (pinfunction "2_2") (pintype "passive"))
      (node (ref "D10") (pin "1") (pinfunction "A_1") (pintype "passive"))
      (node (ref "Q5") (pin "3") (pinfunction "C_3") (pintype "passive"))
    )
    (net (code "51") (name "Net-(D10-K)") (class "Default")
      (node (ref "BZ1") (pin "1") (pinfunction "1_1") (pintype "passive"))
      (node (ref "C19") (pin "2") (pinfunction "2_2") (pintype "passive"))
      (node (ref "D10") (pin "2") (pinfunction "K_2") (pintype "passive"))
      (node (ref "R29") (pin "1") (pinfunction "1_1") (pintype "passive"))
    )
    (net (code "52") (name "Net-(D11-PadA)") (class "Default")
      (node (ref "D11") (pin "A") (pinfunction "A_A") (pintype "passive"))
      (node (ref "R48") (pin "2") (pinfunction "2_2") (pintype "passive"))
    )
    (net (code "53") (name "Net-(D12-PadA)") (class "Default")
      (node (ref "D12") (pin "A") (pinfunction "A_A") (pintype "passive"))
      (node (ref "R49") (pin "2") (pinfunction "2_2") (pintype "passive"))
    )
    (net (code "54") (name "Net-(D13-PadA)") (class "Default")
      (node (ref "D13") (pin "A") (pinfunction "A_A") (pintype "passive"))
      (node (ref "R50") (pin "2") (pinfunction "2_2") (pintype "passive"))
    )
    (net (code "55") (name "Net-(P3-Pad2)") (class "Default")
      (node (ref "P3") (pin "2") (pinfunction "2_2") (pintype "passive"))
      (node (ref "R31") (pin "1") (pinfunction "1_1") (pintype "passive"))
    )
    (net (code "56") (name "Net-(P8-Pad1)") (class "Default")
      (node (ref "P8") (pin "1") (pinfunction "1_1") (pintype "passive"))
      (node (ref "R13") (pin "1") (pinfunction "1_1") (pintype "passive"))
      (node (ref "R14") (pin "1") (pinfunction "1_1") (pintype "passive"))
    )
    (net (code "57") (name "Net-(P8-Pad3)") (class "Default")
      (node (ref "P8") (pin "3") (pinfunction "3_3") (pintype "passive"))
      (node (ref "R14") (pin "2") (pinfunction "2_2") (pintype "passive"))
    )
    (net (code "58") (name "Net-(P9-Pad1)") (class "Default")
      (node (ref "P9") (pin "1") (pinfunction "1_1") (pintype "passive"))
      (node (ref "R17") (pin "1") (pinfunction "1_1") (pintype "passive"))
      (node (ref "R18") (pin "1") (pinfunction "1_1") (pintype "passive"))
    )
    (net (code "59") (name "Net-(P9-Pad3)") (class "Default")
      (node (ref "P9") (pin "3") (pinfunction "3_3") (pintype "passive"))
      (node (ref "R18") (pin "2") (pinfunction "2_2") (pintype "passive"))
    )
    (net (code "60") (name "Net-(P11-Pad3)") (class "Default")
      (node (ref "P11") (pin "3") (pinfunction "3_3") (pintype "passive"))
      (node (ref "R36") (pin "2") (pinfunction "2_2") (pintype "passive"))
    )
    (net (code "61") (name "Net-(P12-Pad3)") (class "Default")
      (node (ref "P12") (pin "3") (pinfunction "3_3") (pintype "passive"))
      (node (ref "R38") (pin "2") (pinfunction "2_2") (pintype "passive"))
    )
    (net (code "62") (name "Net-(Q1-B)") (class "Default")
      (node (ref "Q1") (pin "1") (pinfunction "B_1") (pintype "passive"))
      (node (ref "R8") (pin "2") (pinfunction "2_2") (pintype "passive"))
    )
    (net (code "63") (name "Net-(Q1-C)") (class "Default")
      (node (ref "Q1") (pin "3") (pinfunction "C_3") (pintype "passive"))
      (node (ref "R9") (pin "2") (pinfunction "2_2") (pintype "passive"))
    )
    (net (code "64") (name "Net-(Q2-G)") (class "Default")
      (node (ref "Q2") (pin "1") (pinfunction "G_1") (pintype "passive"))
      (node (ref "R10") (pin "2") (pinfunction "2_2") (pintype "passive"))
      (node (ref "R9") (pin "1") (pinfunction "1_1") (pintype "passive"))
    )
    (net (code "65") (name "Net-(Q3-B)") (class "Default")
      (node (ref "Q3") (pin "1") (pinfunction "B_1") (pintype "passive"))
      (node (ref "R19") (pin "2") (pinfunction "2_2") (pintype "passive"))
      (node (ref "R20") (pin "1") (pinfunction "1_1") (pintype "passive"))
    )
    (net (code "66") (name "Net-(Q3-E)") (class "Default")
      (node (ref "Q3") (pin "2") (pinfunction "E_2") (pintype "passive"))
      (node (ref "R26") (pin "1") (pinfunction "1_1") (pintype "passive"))
      (node (ref "R27") (pin "1") (pinfunction "1_1") (pintype "passive"))
      (node (ref "R28") (pin "1") (pinfunction "1_1") (pintype "passive"))
    )
    (net (code "67") (name "Net-(Q4-B)") (class "Default")
      (node (ref "Q4") (pin "1") (pinfunction "B_1") (pintype "passive"))
      (node (ref "R21") (pin "2") (pinfunction "2_2") (pintype "passive"))
      (node (ref "R22") (pin "1") (pinfunction "1_1") (pintype "passive"))
    )
    (net (code "68") (name "Net-(Q4-E)") (class "Default")
      (node (ref "Q4") (pin "2") (pinfunction "E_2") (pintype "passive"))
      (node (ref "R24") (pin "1") (pinfunction "1_1") (pintype "passive"))
    )
    (net (code "69") (name "Net-(Q5-B)") (class "Default")
      (node (ref "Q5") (pin "1") (pinfunction "B_1") (pintype "passive"))
      (node (ref "R30") (pin "1") (pinfunction "1_1") (pintype "passive"))
    )
    (net (code "70") (name "Net-(Q6-G)") (class "Default")
      (node (ref "Q6") (pin "1") (pinfunction "G_1") (pintype "passive"))
      (node (ref "R40") (pin "1") (pinfunction "1_1") (pintype "passive"))
      (node (ref "R41") (pin "2") (pinfunction "2_2") (pintype "passive"))
    )
    (net (code "71") (name "Net-(Q7-B)") (class "Default")
      (node (ref "Q7") (pin "1") (pinfunction "B_1") (pintype "passive"))
      (node (ref "R39") (pin "2") (pinfunction "2_2") (pintype "passive"))
    )
    (net (code "72") (name "Net-(Q7-C)") (class "Default")
      (node (ref "Q7") (pin "3") (pinfunction "C_3") (pintype "passive"))
      (node (ref "R40") (pin "2") (pinfunction "2_2") (pintype "passive"))
    )
    (net (code "73") (name "Net-(Q8-B)") (class "Default")
      (node (ref "Q8") (pin "1") (pinfunction "B_1") (pintype "passive"))
      (node (ref "R46") (pin "1") (pinfunction "1_1") (pintype "passive"))
      (node (ref "R47") (pin "2") (pinfunction "2_2") (pintype "passive"))
    )
    (net (code "74") (name "Net-(Q8-E)") (class "Default")
      (node (ref "Q8") (pin "2") (pinfunction "E_2") (pintype "passive"))
      (node (ref "R48") (pin "1") (pinfunction "1_1") (pintype "passive"))
      (node (ref "R49") (pin "1") (pinfunction "1_1") (pintype "passive"))
      (node (ref "R50") (pin "1") (pinfunction "1_1") (pintype "passive"))
    )
    (net (code "75") (name "Net-(R12-Pad1)") (class "Default")
      (node (ref "R12") (pin "1") (pinfunction "1_1") (pintype "passive"))
      (node (ref "R13") (pin "2") (pinfunction "2_2") (pintype "passive"))
      (node (ref "S2") (pin "1") (pinfunction "1_1") (pintype "passive"))
    )
    (net (code "76") (name "Net-(R16-Pad1)") (class "Default")
      (node (ref "R16") (pin "1") (pinfunction "1_1") (pintype "passive"))
      (node (ref "R17") (pin "2") (pinfunction "2_2") (pintype "passive"))
      (node (ref "S4") (pin "1") (pinfunction "1_1") (pintype "passive"))
    )
    (net (code "77") (name "Net-(U2-P14_ROLE)") (class "Default")
      (node (ref "R42") (pin "2") (pinfunction "2_2") (pintype "passive"))
      (node (ref "U2") (pin "17") (pinfunction "P14_ROLE_17") (pintype "input"))
    )
    (net (code "78") (name "Net-(U2-RESET_H)") (class "Default")
      (node (ref "R43") (pin "1") (pinfunction "1_1") (pintype "passive"))
      (node (ref "U2") (pin "13") (pinfunction "RESET_H_13") (pintype "input"))
    )
    (net (code "79") (name "VBAT") (class "Default")
      (node (ref "C23") (pin "1") (pinfunction "1_1") (pintype "passive"))
      (node (ref "P16") (pin "1") (pinfunction "1_1") (pintype "passive"))
      (node (ref "Q2") (pin "2") (pinfunction "S_2") (pintype "passive"))
      (node (ref "R10") (pin "1") (pinfunction "1_1") (pintype "passive"))
      (node (ref "R32") (pin "2") (pinfunction "2_2") (pintype "passive"))
    )
    (net (code "80") (name "VBATC") (class "Default")
      (node (ref "C1") (pin "2") (pinfunction "2_2") (pintype "passive"))
      (node (ref "C24") (pin "2") (pinfunction "2_2") (pintype "passive"))
      (node (ref "C25") (pin "1") (pinfunction "1_1") (pintype "passive"))
      (node (ref "C3") (pin "1") (pinfunction "1_1") (pintype "passive"))
      (node (ref "Q2") (pin "3") (pinfunction "D_3") (pintype "passive"))
      (node (ref "R29") (pin "2") (pinfunction "2_2") (pintype "passive"))
      (node (ref "R33") (pin "2") (pinfunction "2_2") (pintype "passive"))
      (node (ref "VR1") (pin "3") (pinfunction "Vin_3") (pintype "passive"))
      (node (ref "VR2") (pin "3") (pinfunction "Vin_3") (pintype "passive"))
    )
    (net (code "81") (name "VBT") (class "Default")
      (node (ref "C21") (pin "2") (pinfunction "2_2") (pintype "passive"))
      (node (ref "C22") (pin "2") (pinfunction "2_2") (pintype "passive"))
      (node (ref "Q6") (pin "3") (pinfunction "D_3") (pintype "passive"))
      (node (ref "R42") (pin "1") (pinfunction "1_1") (pintype "passive"))
      (node (ref "U2") (pin "12") (pinfunction "VCC_12") (pintype "power_in"))
    )
    (net (code "82") (name "VNRF") (class "Default")
      (node (ref "C26") (pin "2") (pinfunction "2_2") (pintype "passive"))
      (node (ref "C27") (pin "1") (pinfunction "1_1") (pintype "passive"))
      (node (ref "P2") (pin "2") (pinfunction "2_2") (pintype "passive"))
      (node (ref "VR2") (pin "2") (pinfunction "Vout_2") (pintype "passive"))
    )
    (net (code "83") (name "unconnected-(U2-NC-Pad2)") (class "Default")
      (node (ref "U2") (pin "2") (pinfunction "NC_2") (pintype "passive"))
    )
    (net (code "84") (name "unconnected-(U2-P01-Pad4)") (class "Default")
      (node (ref "U2") (pin "4") (pinfunction "P01_4") (pintype "passive"))
    )
    (net (code "85") (name "unconnected-(U2-P02-Pad5)") (class "Default")
      (node (ref "U2") (pin "5") (pinfunction "P02_5") (pintype "passive"))
    )
    (net (code "86") (name "unconnected-(U2-P03_AUX-Pad6)") (class "Default")
      (node (ref "U2") (pin "6") (pinfunction "P03_AUX_6") (pintype "output"))
    )
    (net (code "87") (name "unconnected-(U2-P07-Pad10)") (class "Default")
      (node (ref "U2") (pin "10") (pinfunction "P07_10") (pintype "passive"))
    )
    (net (code "88") (name "unconnected-(U2-P10-Pad14)") (class "Default")
      (node (ref "U2") (pin "14") (pinfunction "P10_14") (pintype "passive"))
    )
    (net (code "89") (name "unconnected-(U2-P12-Pad18)") (class "Default")
      (node (ref "U2") (pin "18") (pinfunction "P12_18") (pintype "passive"))
    )
    (net (code "90") (name "unconnected-(U2-P13-Pad19)") (class "Default")
      (node (ref "U2") (pin "19") (pinfunction "P13_19") (pintype "passive"))
    )
    (net (code "91") (name "unconnected-(U2-P15-Pad16)") (class "Default")
      (node (ref "U2") (pin "16") (pinfunction "P15_16") (pintype "passive"))
    )
  )
)
